# supply_LM1117.net
KiCad netlist of a schematic drawn in EAGLE
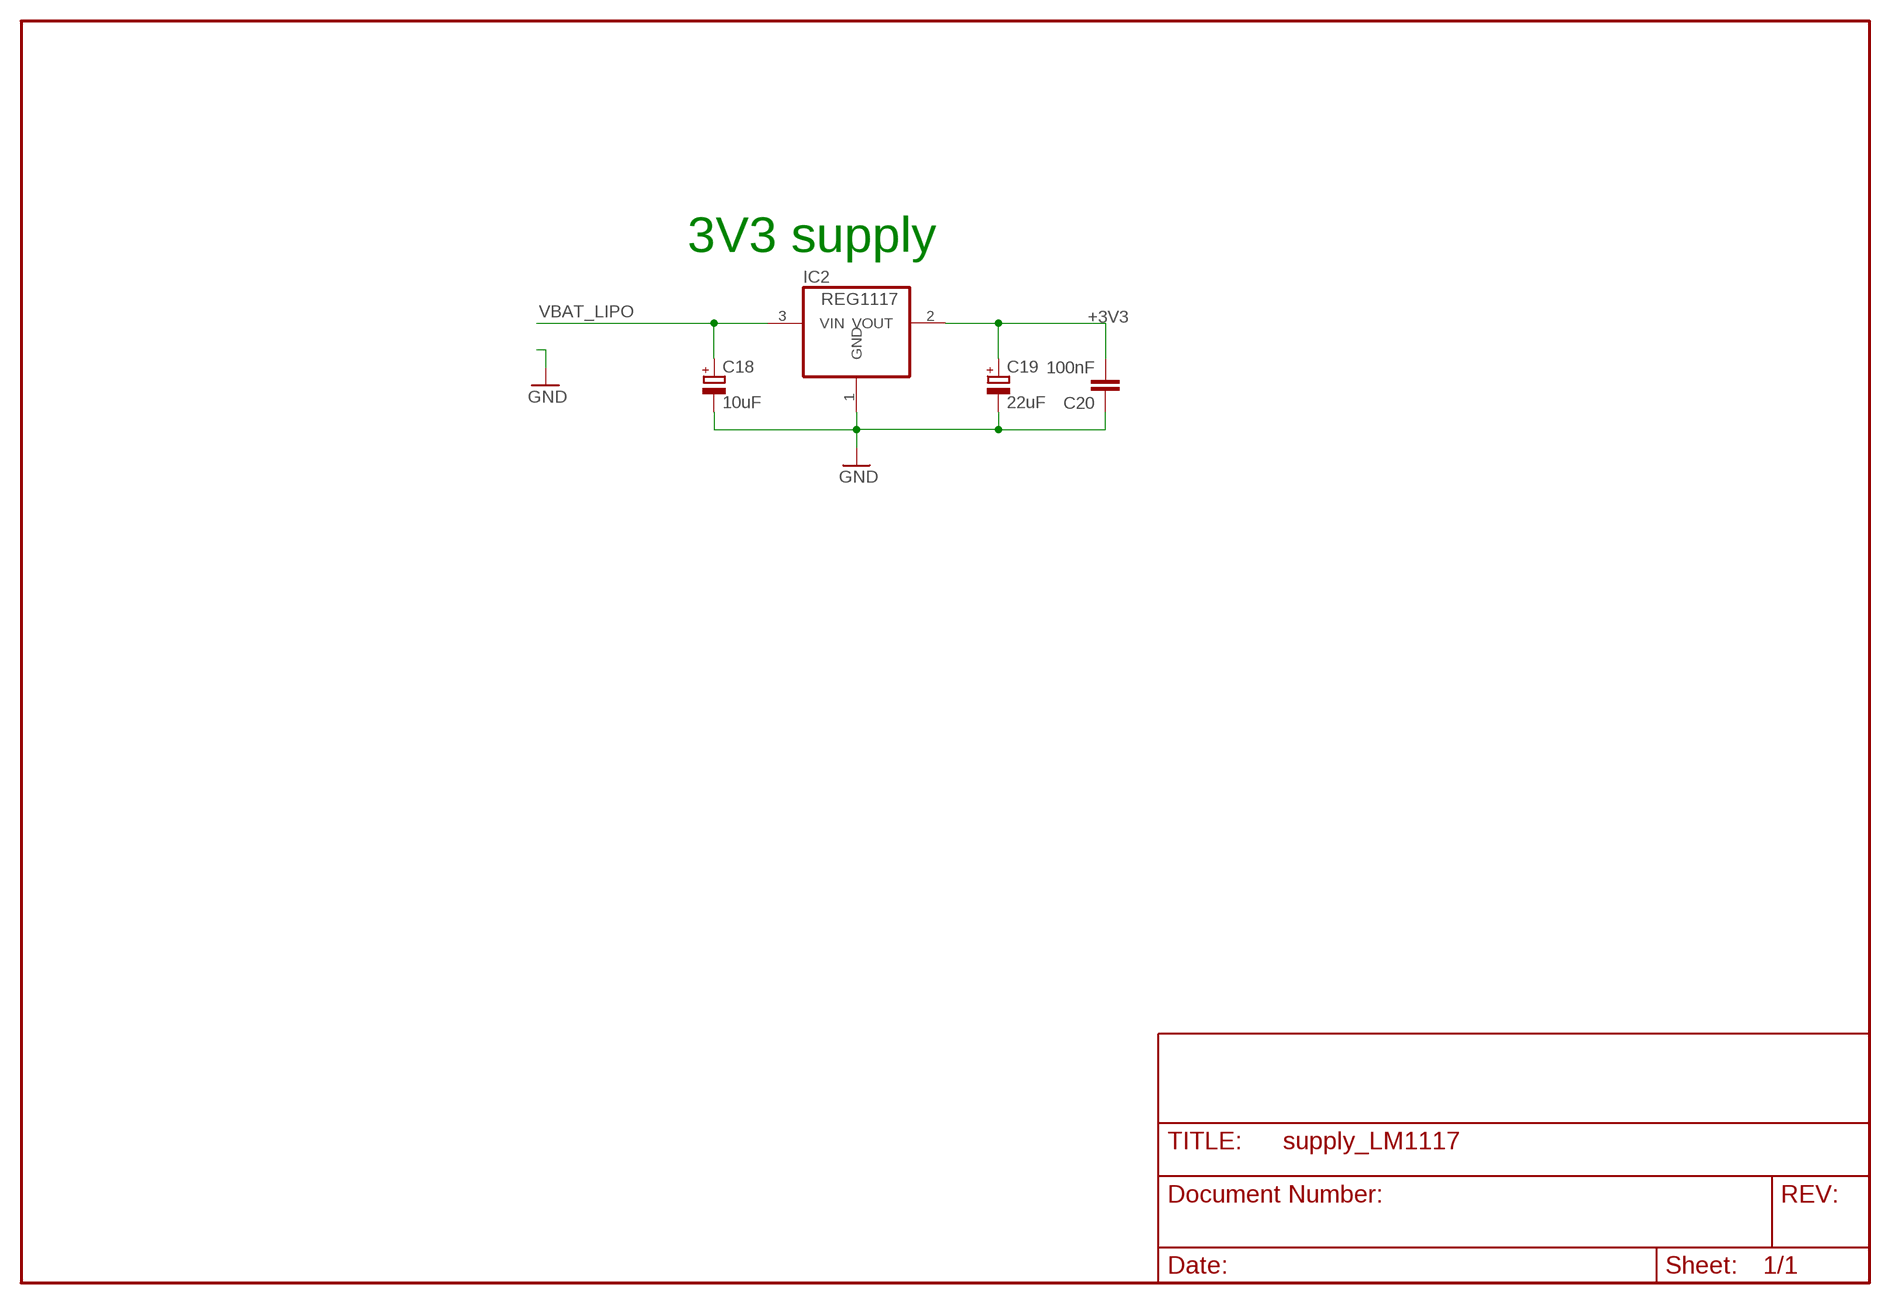
[diagram p0: schematic, sheet 1]

(export (version "E")
  (design (tool "Eeschema 10.0.6"))
  (components
    (comp (ref "C18")
      (value "10uF")
      (footprint "eagle-import:B_3528-21R")
      (libsource (lib "eagle-import") (part "CPOL-EUB/3528-21R"))
    )
    (comp (ref "C19")
      (value "22uF")
      (footprint "eagle-import:B_3528-21R")
      (libsource (lib "eagle-import") (part "CPOL-EUB/3528-21R"))
    )
    (comp (ref "C20")
      (value "100nF")
      (footprint "eagle-import:C0805K")
      (libsource (lib "eagle-import") (part "C-EUC0805K"))
    )
    (comp (ref "IC2")
      (value "REG1117")
      (footprint "eagle-import:SOT223")
      (libsource (lib "eagle-import") (part "REG1117"))
    )
  )
  (nets
    (net (code "1") (name "/+3V3") (class "Default")
      (node (ref "C19") (pin "+") (pinfunction "+_+") (pintype "passive"))
      (node (ref "C20") (pin "2") (pinfunction "2_2") (pintype "passive"))
      (node (ref "IC2") (pin "2") (pinfunction "VOUT_2") (pintype "output"))
    )
    (net (code "2") (name "/VBAT_LIPO") (class "Default")
      (node (ref "C18") (pin "+") (pinfunction "+_+") (pintype "passive"))
      (node (ref "IC2") (pin "3") (pinfunction "VIN_3") (pintype "input"))
    )
    (net (code "3") (name "GND") (class "Default")
      (node (ref "C18") (pin "-") (pinfunction "-_-") (pintype "passive"))
      (node (ref "C19") (pin "-") (pinfunction "-_-") (pintype "passive"))
      (node (ref "C20") (pin "1") (pinfunction "1_1") (pintype "passive"))
      (node (ref "IC2") (pin "1") (pinfunction "GND_1") (pintype "power_in"))
    )
  )
)
